# dc5032018banglet.net
KiCad netlist of a schematic drawn in EAGLE
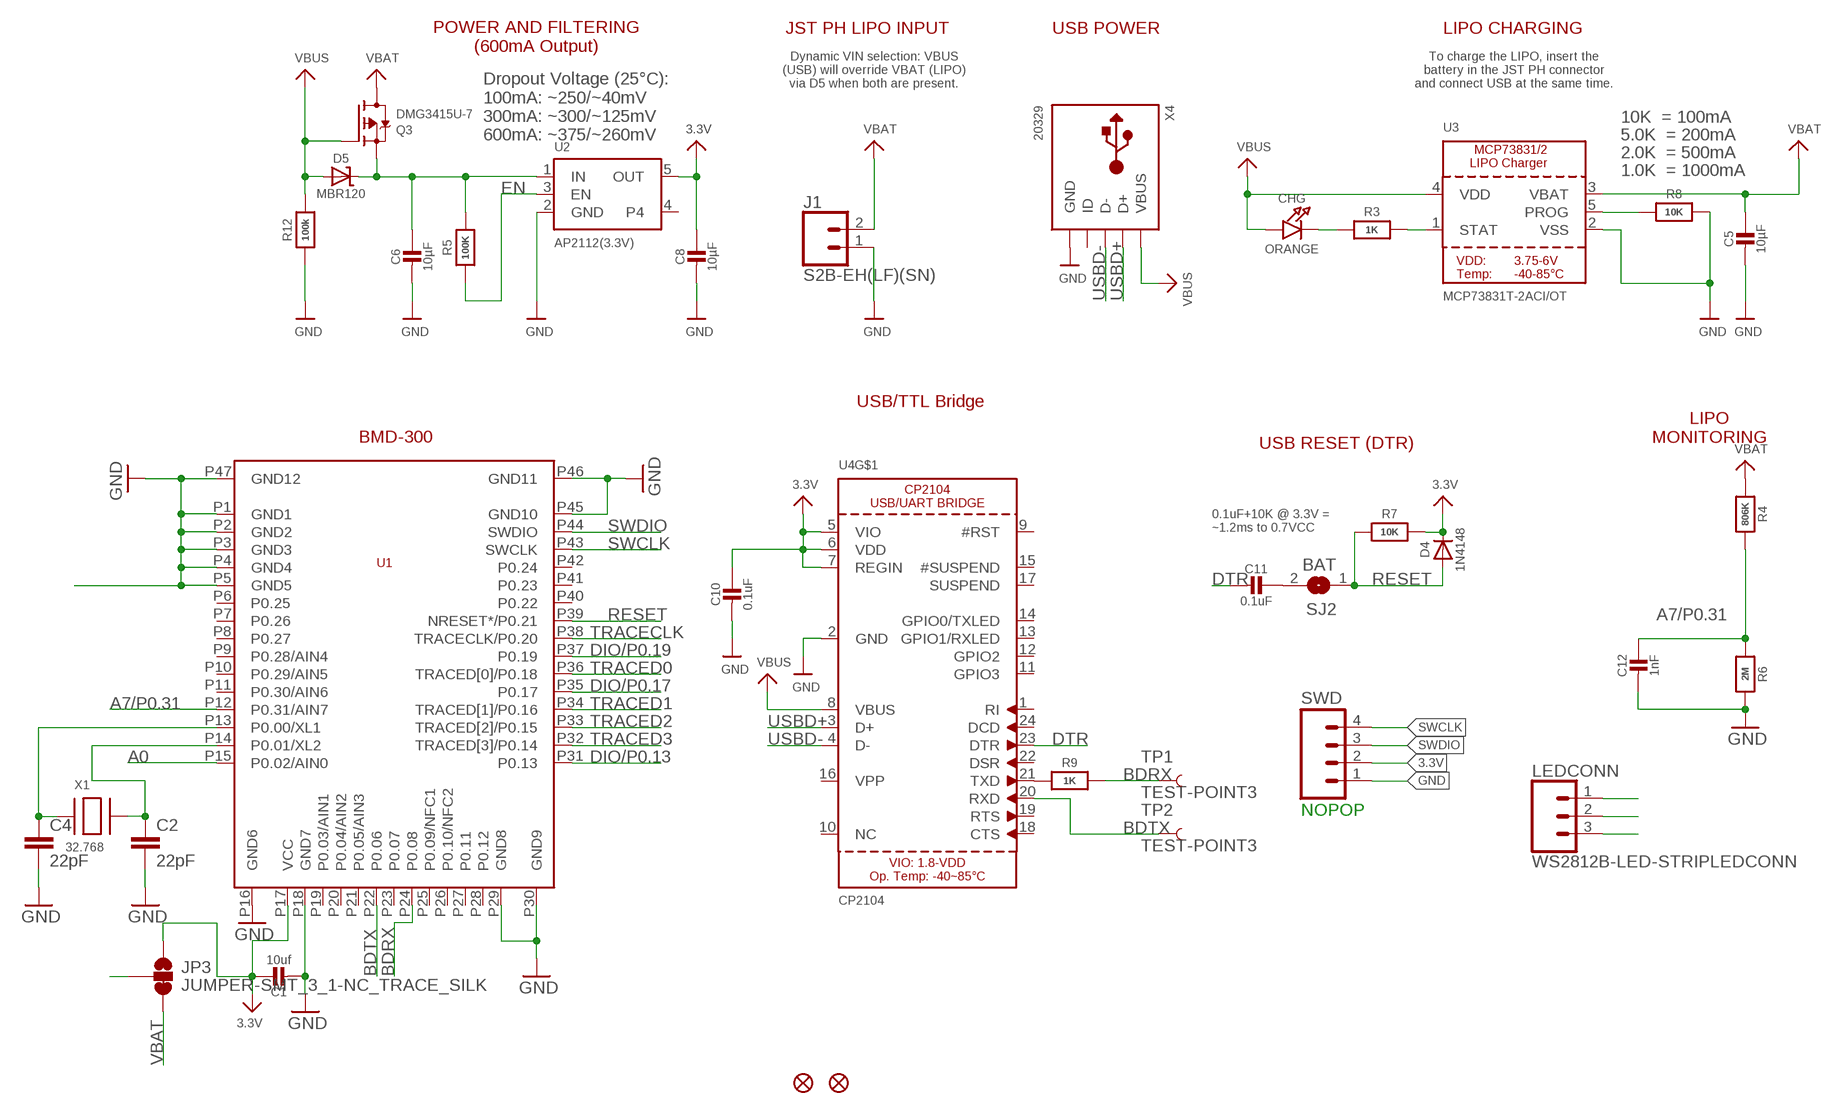
[diagram p0: schematic, sheet 1]

(export (version "E")
  (design (tool "Eeschema 10.0.6"))
  (components
    (comp (ref "C1")
      (value "10uf")
      (footprint "eagle-import:0805-NO")
      (libsource (lib "eagle-import") (part "CAP_CERAMIC0805-NOOUTLINE"))
    )
    (comp (ref "C2")
      (value "22pF")
      (footprint "eagle-import:0603")
      (libsource (lib "eagle-import") (part "22PF-0603-50V-5%"))
    )
    (comp (ref "C4")
      (value "22pF")
      (footprint "eagle-import:0603")
      (libsource (lib "eagle-import") (part "22PF-0603-50V-5%"))
    )
    (comp (ref "C5")
      (value "10µF")
      (footprint "eagle-import:0805-NO")
      (libsource (lib "eagle-import") (part "CAP_CERAMIC0805-NOOUTLINE"))
    )
    (comp (ref "C6")
      (value "10µF")
      (footprint "eagle-import:0805-NO")
      (libsource (lib "eagle-import") (part "CAP_CERAMIC0805-NOOUTLINE"))
    )
    (comp (ref "C8")
      (value "10µF")
      (footprint "eagle-import:0805-NO")
      (libsource (lib "eagle-import") (part "CAP_CERAMIC0805-NOOUTLINE"))
    )
    (comp (ref "C10")
      (value "0.1uF")
      (footprint "eagle-import:0603-NO")
      (libsource (lib "eagle-import") (part "CAP_CERAMIC0603_NO"))
    )
    (comp (ref "C11")
      (value "0.1uF")
      (footprint "eagle-import:0603-NO")
      (libsource (lib "eagle-import") (part "CAP_CERAMIC0603_NO"))
    )
    (comp (ref "C12")
      (value "1nF")
      (footprint "eagle-import:0603-NO")
      (libsource (lib "eagle-import") (part "CAP_CERAMIC0603_NO"))
    )
    (comp (ref "CHG")
      (value "ORANGE")
      (footprint "eagle-import:CHIPLED_0805_NOOUTLINE")
      (libsource (lib "eagle-import") (part "LED0805_NOOUTLINE"))
    )
    (comp (ref "D4")
      (value "1N4148")
      (footprint "eagle-import:SOD-323")
      (libsource (lib "eagle-import") (part "DIODESOD-323"))
    )
    (comp (ref "D5")
      (value "MBR120")
      (footprint "eagle-import:SOD-123")
      (libsource (lib "eagle-import") (part "DIODE-SCHOTTKYSOD-123"))
    )
    (comp (ref "FD1")
      (value "FIDUCIALUFIDUCIAL")
      (footprint "eagle-import:FIDUCIAL-MICRO")
      (libsource (lib "eagle-import") (part "FIDUCIALUFIDUCIAL"))
    )
    (comp (ref "FD2")
      (value "FIDUCIALUFIDUCIAL")
      (footprint "eagle-import:FIDUCIAL-MICRO")
      (libsource (lib "eagle-import") (part "FIDUCIALUFIDUCIAL"))
    )
    (comp (ref "J1")
      (value "S2B-EH(LF)(SN)")
      (footprint "eagle-import:1X2(2.5)")
      (libsource (lib "eagle-import") (part "S2B-EH(LF)(SN)"))
    )
    (comp (ref "JP3")
      (value "JUMPER-SMT_3_1-NC_TRACE_SILK")
      (footprint "eagle-import:SMT-JUMPER_3_1-NC_TRACE_SILK")
      (libsource (lib "eagle-import") (part "JUMPER-SMT_3_1-NC_TRACE_SILK"))
    )
    (comp (ref "LEDCONN")
      (value "WS2812B-LED-STRIPLEDCONN")
      (footprint "eagle-import:1X3(2.5)")
      (libsource (lib "eagle-import") (part "WS2812B-LED-STRIPLEDCONN"))
    )
    (comp (ref "Q3")
      (value "DMG3415U-7")
      (footprint "eagle-import:SOT23-R")
      (libsource (lib "eagle-import") (part "MOSFET-P"))
    )
    (comp (ref "R3")
      (value "1K")
      (footprint "eagle-import:0603-NO")
      (libsource (lib "eagle-import") (part "RESISTOR_0603_NOOUT"))
    )
    (comp (ref "R4")
      (value "806K")
      (footprint "eagle-import:0603-NO")
      (libsource (lib "eagle-import") (part "RESISTOR_0603_NOOUT"))
    )
    (comp (ref "R5")
      (value "100K")
      (footprint "eagle-import:0603-NO")
      (libsource (lib "eagle-import") (part "RESISTOR_0603_NOOUT"))
    )
    (comp (ref "R6")
      (value "2M")
      (footprint "eagle-import:0603-NO")
      (libsource (lib "eagle-import") (part "RESISTOR_0603_NOOUT"))
    )
    (comp (ref "R7")
      (value "10K")
      (footprint "eagle-import:0603-NO")
      (libsource (lib "eagle-import") (part "RESISTOR_0603_NOOUT"))
    )
    (comp (ref "R8")
      (value "10K")
      (footprint "eagle-import:0603-NO")
      (libsource (lib "eagle-import") (part "RESISTOR_0603_NOOUT"))
    )
    (comp (ref "R9")
      (value "1K")
      (footprint "eagle-import:0603-NO")
      (libsource (lib "eagle-import") (part "RESISTOR_0603_NOOUT"))
    )
    (comp (ref "R12")
      (value "100k")
      (footprint "eagle-import:0603-NO")
      (libsource (lib "eagle-import") (part "RESISTOR_0603_NOOUT"))
    )
    (comp (ref "SJ2")
      (value "BAT")
      (footprint "eagle-import:SOLDERJUMPER_CLOSEDWIRE")
      (libsource (lib "eagle-import") (part "SOLDERJUMPERCLOSED"))
    )
    (comp (ref "SWD")
      (value "M04LOCK")
      (footprint "eagle-import:1X04_LOCK@1")
      (libsource (lib "eagle-import") (part "M04LOCK"))
    )
    (comp (ref "TP1")
      (value "TEST-POINT3")
      (footprint "eagle-import:PAD.03X.03")
      (libsource (lib "eagle-import") (part "TEST-POINT3"))
    )
    (comp (ref "TP2")
      (value "TEST-POINT3")
      (footprint "eagle-import:PAD.03X.03")
      (libsource (lib "eagle-import") (part "TEST-POINT3"))
    )
    (comp (ref "U1")
      (value "BMD-300")
      (footprint "eagle-import:BMD-300")
      (libsource (lib "eagle-import") (part "BMD-300"))
    )
    (comp (ref "U2")
      (value "AP2112(3.3V)")
      (footprint "eagle-import:SOT23-5")
      (libsource (lib "eagle-import") (part "VREG_SOT23-5"))
    )
    (comp (ref "U3")
      (value "MCP73831T-2ACI/OT")
      (footprint "eagle-import:SOT23-5")
      (libsource (lib "eagle-import") (part "MCP73831/2"))
    )
    (comp (ref "U4")
      (value "CP2104")
      (footprint "eagle-import:QFN24_4MM_SMSC")
      (libsource (lib "eagle-import") (part "CP2104"))
    )
    (comp (ref "X1")
      (value "32.768")
      (footprint "eagle-import:XTAL3215")
      (libsource (lib "eagle-import") (part "XTAL-3.2X1.5"))
    )
    (comp (ref "X4")
      (value "20329")
      (footprint "eagle-import:MICRO-USB5+6P-SMD-0.65-B")
      (libsource (lib "eagle-import") (part "MICRO-USB-SMD-B-(10118193-0001LF)-ADASYM"))
    )
  )
  (nets
    (net (code "1") (name "/A0") (class "Default")
      (node (ref "LEDCONN") (pin "2") (pinfunction "2_2") (pintype "passive"))
      (node (ref "U1") (pin "P15") (pinfunction "P0.02/AIN0_P15") (pintype "bidirectional"))
    )
    (net (code "2") (name "/A7{slash}P0.31") (class "Default")
      (node (ref "C12") (pin "1") (pinfunction "1_1") (pintype "passive"))
      (node (ref "R4") (pin "2") (pinfunction "2_2") (pintype "passive"))
      (node (ref "R6") (pin "1") (pinfunction "1_1") (pintype "passive"))
      (node (ref "U1") (pin "P12") (pinfunction "P0.31/AIN7_P12") (pintype "bidirectional"))
    )
    (net (code "3") (name "/BDRX") (class "Default")
      (node (ref "R9") (pin "2") (pinfunction "2_2") (pintype "passive"))
      (node (ref "TP1") (pin "P$1") (pinfunction "1_P$1") (pintype "bidirectional"))
      (node (ref "U1") (pin "P24") (pinfunction "P0.08_P24") (pintype "bidirectional"))
    )
    (net (code "4") (name "/BDTX") (class "Default")
      (node (ref "TP2") (pin "P$1") (pinfunction "1_P$1") (pintype "bidirectional"))
      (node (ref "U1") (pin "P22") (pinfunction "P0.06_P22") (pintype "bidirectional"))
      (node (ref "U4") (pin "20") (pinfunction "RXD_20") (pintype "input"))
    )
    (net (code "5") (name "/DIO{slash}P0.13") (class "Default")
      (node (ref "U1") (pin "P31") (pinfunction "P0.13_P31") (pintype "bidirectional"))
    )
    (net (code "6") (name "/DIO{slash}P0.17") (class "Default")
      (node (ref "U1") (pin "P35") (pinfunction "P0.17_P35") (pintype "bidirectional"))
    )
    (net (code "7") (name "/DIO{slash}P0.19") (class "Default")
      (node (ref "U1") (pin "P37") (pinfunction "P0.19_P37") (pintype "bidirectional"))
    )
    (net (code "8") (name "/DTR") (class "Default")
      (node (ref "C11") (pin "2") (pinfunction "2_2") (pintype "passive"))
      (node (ref "U4") (pin "23") (pinfunction "DTR_23") (pintype "output"))
    )
    (net (code "9") (name "/EN") (class "Default")
      (node (ref "R5") (pin "1") (pinfunction "1_1") (pintype "passive"))
      (node (ref "U2") (pin "3") (pinfunction "EN_3") (pintype "input"))
    )
    (net (code "10") (name "/RESET") (class "Default")
      (node (ref "D4") (pin "A") (pinfunction "A_A") (pintype "passive"))
      (node (ref "R7") (pin "1") (pinfunction "1_1") (pintype "passive"))
      (node (ref "SJ2") (pin "1") (pinfunction "1_1") (pintype "passive"))
      (node (ref "U1") (pin "P39") (pinfunction "NRESET*/P0.21_P39") (pintype "bidirectional"))
    )
    (net (code "11") (name "/TRACECLK") (class "Default")
      (node (ref "U1") (pin "P38") (pinfunction "TRACECLK/P0.20_P38") (pintype "bidirectional"))
    )
    (net (code "12") (name "/TRACED0") (class "Default")
      (node (ref "U1") (pin "P36") (pinfunction "TRACED[0]/P0.18_P36") (pintype "bidirectional"))
    )
    (net (code "13") (name "/TRACED1") (class "Default")
      (node (ref "U1") (pin "P34") (pinfunction "TRACED[1]/P0.16_P34") (pintype "bidirectional"))
    )
    (net (code "14") (name "/TRACED2") (class "Default")
      (node (ref "U1") (pin "P33") (pinfunction "TRACED[2]/P0.15_P33") (pintype "bidirectional"))
    )
    (net (code "15") (name "/TRACED3") (class "Default")
      (node (ref "U1") (pin "P32") (pinfunction "TRACED[3]/P0.14_P32") (pintype "bidirectional"))
    )
    (net (code "16") (name "/USBD+") (class "Default")
      (node (ref "U4") (pin "3") (pinfunction "D+_3") (pintype "bidirectional"))
      (node (ref "X4") (pin "3") (pinfunction "D+_3") (pintype "bidirectional"))
    )
    (net (code "17") (name "/USBD-") (class "Default")
      (node (ref "U4") (pin "4") (pinfunction "D-_4") (pintype "bidirectional"))
      (node (ref "X4") (pin "2") (pinfunction "D-_2") (pintype "bidirectional"))
    )
    (net (code "18") (name "/VLED") (class "Default")
      (node (ref "JP3") (pin "2") (pinfunction "2_2") (pintype "passive"))
      (node (ref "LEDCONN") (pin "1") (pinfunction "1_1") (pintype "passive"))
    )
    (net (code "19") (name "3.3V") (class "Default")
      (node (ref "C1") (pin "1") (pinfunction "1_1") (pintype "passive"))
      (node (ref "C10") (pin "1") (pinfunction "1_1") (pintype "passive"))
      (node (ref "C8") (pin "1") (pinfunction "1_1") (pintype "passive"))
      (node (ref "D4") (pin "C") (pinfunction "C_C") (pintype "passive"))
      (node (ref "JP3") (pin "1") (pinfunction "1_1") (pintype "passive"))
      (node (ref "R7") (pin "2") (pinfunction "2_2") (pintype "passive"))
      (node (ref "SWD") (pin "2") (pinfunction "2_2") (pintype "passive"))
      (node (ref "U1") (pin "P17") (pinfunction "VCC_P17") (pintype "bidirectional"))
      (node (ref "U2") (pin "5") (pinfunction "OUT_5") (pintype "power_in"))
      (node (ref "U4") (pin "5") (pinfunction "VIO_5") (pintype "power_in"))
      (node (ref "U4") (pin "6") (pinfunction "VDD_6") (pintype "power_in"))
      (node (ref "U4") (pin "7") (pinfunction "REGIN_7") (pintype "power_in"))
    )
    (net (code "20") (name "GND") (class "Default")
      (node (ref "C1") (pin "2") (pinfunction "2_2") (pintype "passive"))
      (node (ref "C10") (pin "2") (pinfunction "2_2") (pintype "passive"))
      (node (ref "C12") (pin "2") (pinfunction "2_2") (pintype "passive"))
      (node (ref "C2") (pin "2") (pinfunction "2_2") (pintype "passive"))
      (node (ref "C4") (pin "2") (pinfunction "2_2") (pintype "passive"))
      (node (ref "C5") (pin "2") (pinfunction "2_2") (pintype "passive"))
      (node (ref "C6") (pin "2") (pinfunction "2_2") (pintype "passive"))
      (node (ref "C8") (pin "2") (pinfunction "2_2") (pintype "passive"))
      (node (ref "J1") (pin "1") (pinfunction "1_1") (pintype "passive"))
      (node (ref "LEDCONN") (pin "3") (pinfunction "3_3") (pintype "passive"))
      (node (ref "R12") (pin "1") (pinfunction "1_1") (pintype "passive"))
      (node (ref "R6") (pin "2") (pinfunction "2_2") (pintype "passive"))
      (node (ref "R8") (pin "2") (pinfunction "2_2") (pintype "passive"))
      (node (ref "SWD") (pin "1") (pinfunction "1_1") (pintype "passive"))
      (node (ref "U1") (pin "P1") (pinfunction "GND1_P1") (pintype "bidirectional"))
      (node (ref "U1") (pin "P16") (pinfunction "GND6_P16") (pintype "bidirectional"))
      (node (ref "U1") (pin "P18") (pinfunction "GND7_P18") (pintype "bidirectional"))
      (node (ref "U1") (pin "P2") (pinfunction "GND2_P2") (pintype "bidirectional"))
      (node (ref "U1") (pin "P29") (pinfunction "GND8_P29") (pintype "bidirectional"))
      (node (ref "U1") (pin "P3") (pinfunction "GND3_P3") (pintype "bidirectional"))
      (node (ref "U1") (pin "P30") (pinfunction "GND9_P30") (pintype "bidirectional"))
      (node (ref "U1") (pin "P4") (pinfunction "GND4_P4") (pintype "bidirectional"))
      (node (ref "U1") (pin "P45") (pinfunction "GND10_P45") (pintype "bidirectional"))
      (node (ref "U1") (pin "P46") (pinfunction "GND11_P46") (pintype "bidirectional"))
      (node (ref "U1") (pin "P47") (pinfunction "GND12_P47") (pintype "bidirectional"))
      (node (ref "U1") (pin "P5") (pinfunction "GND5_P5") (pintype "bidirectional"))
      (node (ref "U2") (pin "2") (pinfunction "GND_2") (pintype "power_in"))
      (node (ref "U3") (pin "2") (pinfunction "VSS_2") (pintype "power_in"))
      (node (ref "U4") (pin "2") (pinfunction "GND_2") (pintype "power_in"))
      (node (ref "X4") (pin "5") (pinfunction "GND_5") (pintype "power_in"))
      (node (ref "X4") (pin "S1") (pinfunction "GND_S1") (pintype "power_in"))
      (node (ref "X4") (pin "S2") (pinfunction "GND_S2") (pintype "power_in"))
      (node (ref "X4") (pin "S3") (pinfunction "GND_S3") (pintype "power_in"))
      (node (ref "X4") (pin "S4") (pinfunction "GND_S4") (pintype "power_in"))
      (node (ref "X4") (pin "S5") (pinfunction "GND_S5") (pintype "power_in"))
      (node (ref "X4") (pin "S6") (pinfunction "GND_S6") (pintype "power_in"))
    )
    (net (code "21") (name "Net-(C11-Pad1)") (class "Default")
      (node (ref "C11") (pin "1") (pinfunction "1_1") (pintype "passive"))
      (node (ref "SJ2") (pin "2") (pinfunction "2_2") (pintype "passive"))
    )
    (net (code "22") (name "Net-(CHG-PadC)") (class "Default")
      (node (ref "CHG") (pin "C") (pinfunction "C_C") (pintype "passive"))
      (node (ref "R3") (pin "1") (pinfunction "1_1") (pintype "passive"))
    )
    (net (code "23") (name "Net-(Q3-S)") (class "Default")
      (node (ref "C6") (pin "1") (pinfunction "1_1") (pintype "passive"))
      (node (ref "D5") (pin "C") (pinfunction "C_C") (pintype "passive"))
      (node (ref "Q3") (pin "2") (pinfunction "S_2") (pintype "passive"))
      (node (ref "R5") (pin "2") (pinfunction "2_2") (pintype "passive"))
      (node (ref "U2") (pin "1") (pinfunction "IN_1") (pintype "power_in"))
    )
    (net (code "24") (name "Net-(U1-P0.00{slash}XL1)") (class "Default")
      (node (ref "C4") (pin "1") (pinfunction "1_1") (pintype "passive"))
      (node (ref "U1") (pin "P13") (pinfunction "P0.00/XL1_P13") (pintype "bidirectional"))
      (node (ref "X1") (pin "P$1") (pinfunction "P$1_P$1") (pintype "bidirectional"))
    )
    (net (code "25") (name "Net-(U1-P0.01{slash}XL2)") (class "Default")
      (node (ref "C2") (pin "1") (pinfunction "1_1") (pintype "passive"))
      (node (ref "U1") (pin "P14") (pinfunction "P0.01/XL2_P14") (pintype "bidirectional"))
      (node (ref "X1") (pin "P$2") (pinfunction "P$2_P$2") (pintype "bidirectional"))
    )
    (net (code "26") (name "Net-(U3-PROG)") (class "Default")
      (node (ref "R8") (pin "1") (pinfunction "1_1") (pintype "passive"))
      (node (ref "U3") (pin "5") (pinfunction "PROG_5") (pintype "input"))
    )
    (net (code "27") (name "Net-(U3-STAT)") (class "Default")
      (node (ref "R3") (pin "2") (pinfunction "2_2") (pintype "passive"))
      (node (ref "U3") (pin "1") (pinfunction "STAT_1") (pintype "output"))
    )
    (net (code "28") (name "Net-(U4A-TXD)") (class "Default")
      (node (ref "R9") (pin "1") (pinfunction "1_1") (pintype "passive"))
      (node (ref "U4") (pin "21") (pinfunction "TXD_21") (pintype "output"))
    )
    (net (code "29") (name "SWCLK") (class "Default")
      (node (ref "SWD") (pin "4") (pinfunction "4_4") (pintype "passive"))
      (node (ref "U1") (pin "P43") (pinfunction "SWCLK_P43") (pintype "bidirectional"))
    )
    (net (code "30") (name "SWDIO") (class "Default")
      (node (ref "SWD") (pin "3") (pinfunction "3_3") (pintype "passive"))
      (node (ref "U1") (pin "P44") (pinfunction "SWDIO_P44") (pintype "bidirectional"))
    )
    (net (code "31") (name "VBAT") (class "Default")
      (node (ref "C5") (pin "1") (pinfunction "1_1") (pintype "passive"))
      (node (ref "J1") (pin "2") (pinfunction "2_2") (pintype "passive"))
      (node (ref "JP3") (pin "3") (pinfunction "3_3") (pintype "passive"))
      (node (ref "Q3") (pin "3") (pinfunction "D_3") (pintype "passive"))
      (node (ref "R4") (pin "1") (pinfunction "1_1") (pintype "passive"))
      (node (ref "U3") (pin "3") (pinfunction "VBAT_3") (pintype "power_in"))
    )
    (net (code "32") (name "VBUS") (class "Default")
      (node (ref "CHG") (pin "A") (pinfunction "A_A") (pintype "passive"))
      (node (ref "D5") (pin "A") (pinfunction "A_A") (pintype "passive"))
      (node (ref "Q3") (pin "1") (pinfunction "G_1") (pintype "passive"))
      (node (ref "R12") (pin "2") (pinfunction "2_2") (pintype "passive"))
      (node (ref "U3") (pin "4") (pinfunction "VDD_4") (pintype "power_in"))
      (node (ref "U4") (pin "8") (pinfunction "VBUS_8") (pintype "power_in"))
      (node (ref "X4") (pin "1") (pinfunction "VBUS_1") (pintype "power_in"))
    )
    (net (code "33") (name "unconnected-(U1-P0.03{slash}AIN1-PadP19)") (class "Default")
      (node (ref "U1") (pin "P19") (pinfunction "P0.03/AIN1_P19") (pintype "bidirectional"))
    )
    (net (code "34") (name "unconnected-(U1-P0.04{slash}AIN2-PadP20)") (class "Default")
      (node (ref "U1") (pin "P20") (pinfunction "P0.04/AIN2_P20") (pintype "bidirectional"))
    )
    (net (code "35") (name "unconnected-(U1-P0.05{slash}AIN3-PadP21)") (class "Default")
      (node (ref "U1") (pin "P21") (pinfunction "P0.05/AIN3_P21") (pintype "bidirectional"))
    )
    (net (code "36") (name "unconnected-(U1-P0.07-PadP23)") (class "Default")
      (node (ref "U1") (pin "P23") (pinfunction "P0.07_P23") (pintype "bidirectional"))
    )
    (net (code "37") (name "unconnected-(U1-P0.09{slash}NFC1-PadP25)") (class "Default")
      (node (ref "U1") (pin "P25") (pinfunction "P0.09/NFC1_P25") (pintype "bidirectional"))
    )
    (net (code "38") (name "unconnected-(U1-P0.10{slash}NFC2-PadP26)") (class "Default")
      (node (ref "U1") (pin "P26") (pinfunction "P0.10/NFC2_P26") (pintype "bidirectional"))
    )
    (net (code "39") (name "unconnected-(U1-P0.11-PadP27)") (class "Default")
      (node (ref "U1") (pin "P27") (pinfunction "P0.11_P27") (pintype "bidirectional"))
    )
    (net (code "40") (name "unconnected-(U1-P0.12-PadP28)") (class "Default")
      (node (ref "U1") (pin "P28") (pinfunction "P0.12_P28") (pintype "bidirectional"))
    )
    (net (code "41") (name "unconnected-(U1-P0.22-PadP40)") (class "Default")
      (node (ref "U1") (pin "P40") (pinfunction "P0.22_P40") (pintype "bidirectional"))
    )
    (net (code "42") (name "unconnected-(U1-P0.23-PadP41)") (class "Default")
      (node (ref "U1") (pin "P41") (pinfunction "P0.23_P41") (pintype "bidirectional"))
    )
    (net (code "43") (name "unconnected-(U1-P0.24-PadP42)") (class "Default")
      (node (ref "U1") (pin "P42") (pinfunction "P0.24_P42") (pintype "bidirectional"))
    )
    (net (code "44") (name "unconnected-(U1-P0.25-PadP6)") (class "Default")
      (node (ref "U1") (pin "P6") (pinfunction "P0.25_P6") (pintype "bidirectional"))
    )
    (net (code "45") (name "unconnected-(U1-P0.26-PadP7)") (class "Default")
      (node (ref "U1") (pin "P7") (pinfunction "P0.26_P7") (pintype "bidirectional"))
    )
    (net (code "46") (name "unconnected-(U1-P0.27-PadP8)") (class "Default")
      (node (ref "U1") (pin "P8") (pinfunction "P0.27_P8") (pintype "bidirectional"))
    )
    (net (code "47") (name "unconnected-(U1-P0.28{slash}AIN4-PadP9)") (class "Default")
      (node (ref "U1") (pin "P9") (pinfunction "P0.28/AIN4_P9") (pintype "bidirectional"))
    )
    (net (code "48") (name "unconnected-(U1-P0.29{slash}AIN5-PadP10)") (class "Default")
      (node (ref "U1") (pin "P10") (pinfunction "P0.29/AIN5_P10") (pintype "bidirectional"))
    )
    (net (code "49") (name "unconnected-(U1-P0.30{slash}AIN6-PadP11)") (class "Default")
      (node (ref "U1") (pin "P11") (pinfunction "P0.30/AIN6_P11") (pintype "bidirectional"))
    )
    (net (code "50") (name "unconnected-(U2-P4-Pad4)") (class "Default")
      (node (ref "U2") (pin "4") (pinfunction "P4_4") (pintype "bidirectional"))
    )
    (net (code "51") (name "unconnected-(U4A-#RST-Pad9)") (class "Default")
      (node (ref "U4") (pin "9") (pinfunction "#RST_9") (pintype "bidirectional"))
    )
    (net (code "52") (name "unconnected-(U4A-#SUSPEND-Pad15)") (class "Default")
      (node (ref "U4") (pin "15") (pinfunction "#SUSPEND_15") (pintype "output"))
    )
    (net (code "53") (name "unconnected-(U4A-CTS-Pad18)") (class "Default")
      (node (ref "U4") (pin "18") (pinfunction "CTS_18") (pintype "input"))
    )
    (net (code "54") (name "unconnected-(U4A-DCD-Pad24)") (class "Default")
      (node (ref "U4") (pin "24") (pinfunction "DCD_24") (pintype "input"))
    )
    (net (code "55") (name "unconnected-(U4A-DSR-Pad22)") (class "Default")
      (node (ref "U4") (pin "22") (pinfunction "DSR_22") (pintype "input"))
    )
    (net (code "56") (name "unconnected-(U4A-GPIO0{slash}TXLED-Pad14)") (class "Default")
      (node (ref "U4") (pin "14") (pinfunction "GPIO0/TXLED_14") (pintype "bidirectional"))
    )
    (net (code "57") (name "unconnected-(U4A-GPIO1{slash}RXLED-Pad13)") (class "Default")
      (node (ref "U4") (pin "13") (pinfunction "GPIO1/RXLED_13") (pintype "bidirectional"))
    )
    (net (code "58") (name "unconnected-(U4A-GPIO2-Pad12)") (class "Default")
      (node (ref "U4") (pin "12") (pinfunction "GPIO2_12") (pintype "bidirectional"))
    )
    (net (code "59") (name "unconnected-(U4A-GPIO3-Pad11)") (class "Default")
      (node (ref "U4") (pin "11") (pinfunction "GPIO3_11") (pintype "bidirectional"))
    )
    (net (code "60") (name "unconnected-(U4A-NC-Pad10)") (class "Default")
      (node (ref "U4") (pin "10") (pinfunction "NC_10") (pintype "no_connect"))
    )
    (net (code "61") (name "unconnected-(U4A-RI-Pad1)") (class "Default")
      (node (ref "U4") (pin "1") (pinfunction "RI_1") (pintype "input"))
    )
    (net (code "62") (name "unconnected-(U4A-RTS-Pad19)") (class "Default")
      (node (ref "U4") (pin "19") (pinfunction "RTS_19") (pintype "output"))
    )
    (net (code "63") (name "unconnected-(U4A-SUSPEND-Pad17)") (class "Default")
      (node (ref "U4") (pin "17") (pinfunction "SUSPEND_17") (pintype "output"))
    )
    (net (code "64") (name "unconnected-(U4A-VPP-Pad16)") (class "Default")
      (node (ref "U4") (pin "16") (pinfunction "VPP_16") (pintype "bidirectional"))
    )
    (net (code "65") (name "unconnected-(X4-ID-Pad4)") (class "Default")
      (node (ref "X4") (pin "4") (pinfunction "ID_4") (pintype "bidirectional"))
    )
  )
)
